# HV.net
KiCad netlist of a schematic drawn in EAGLE
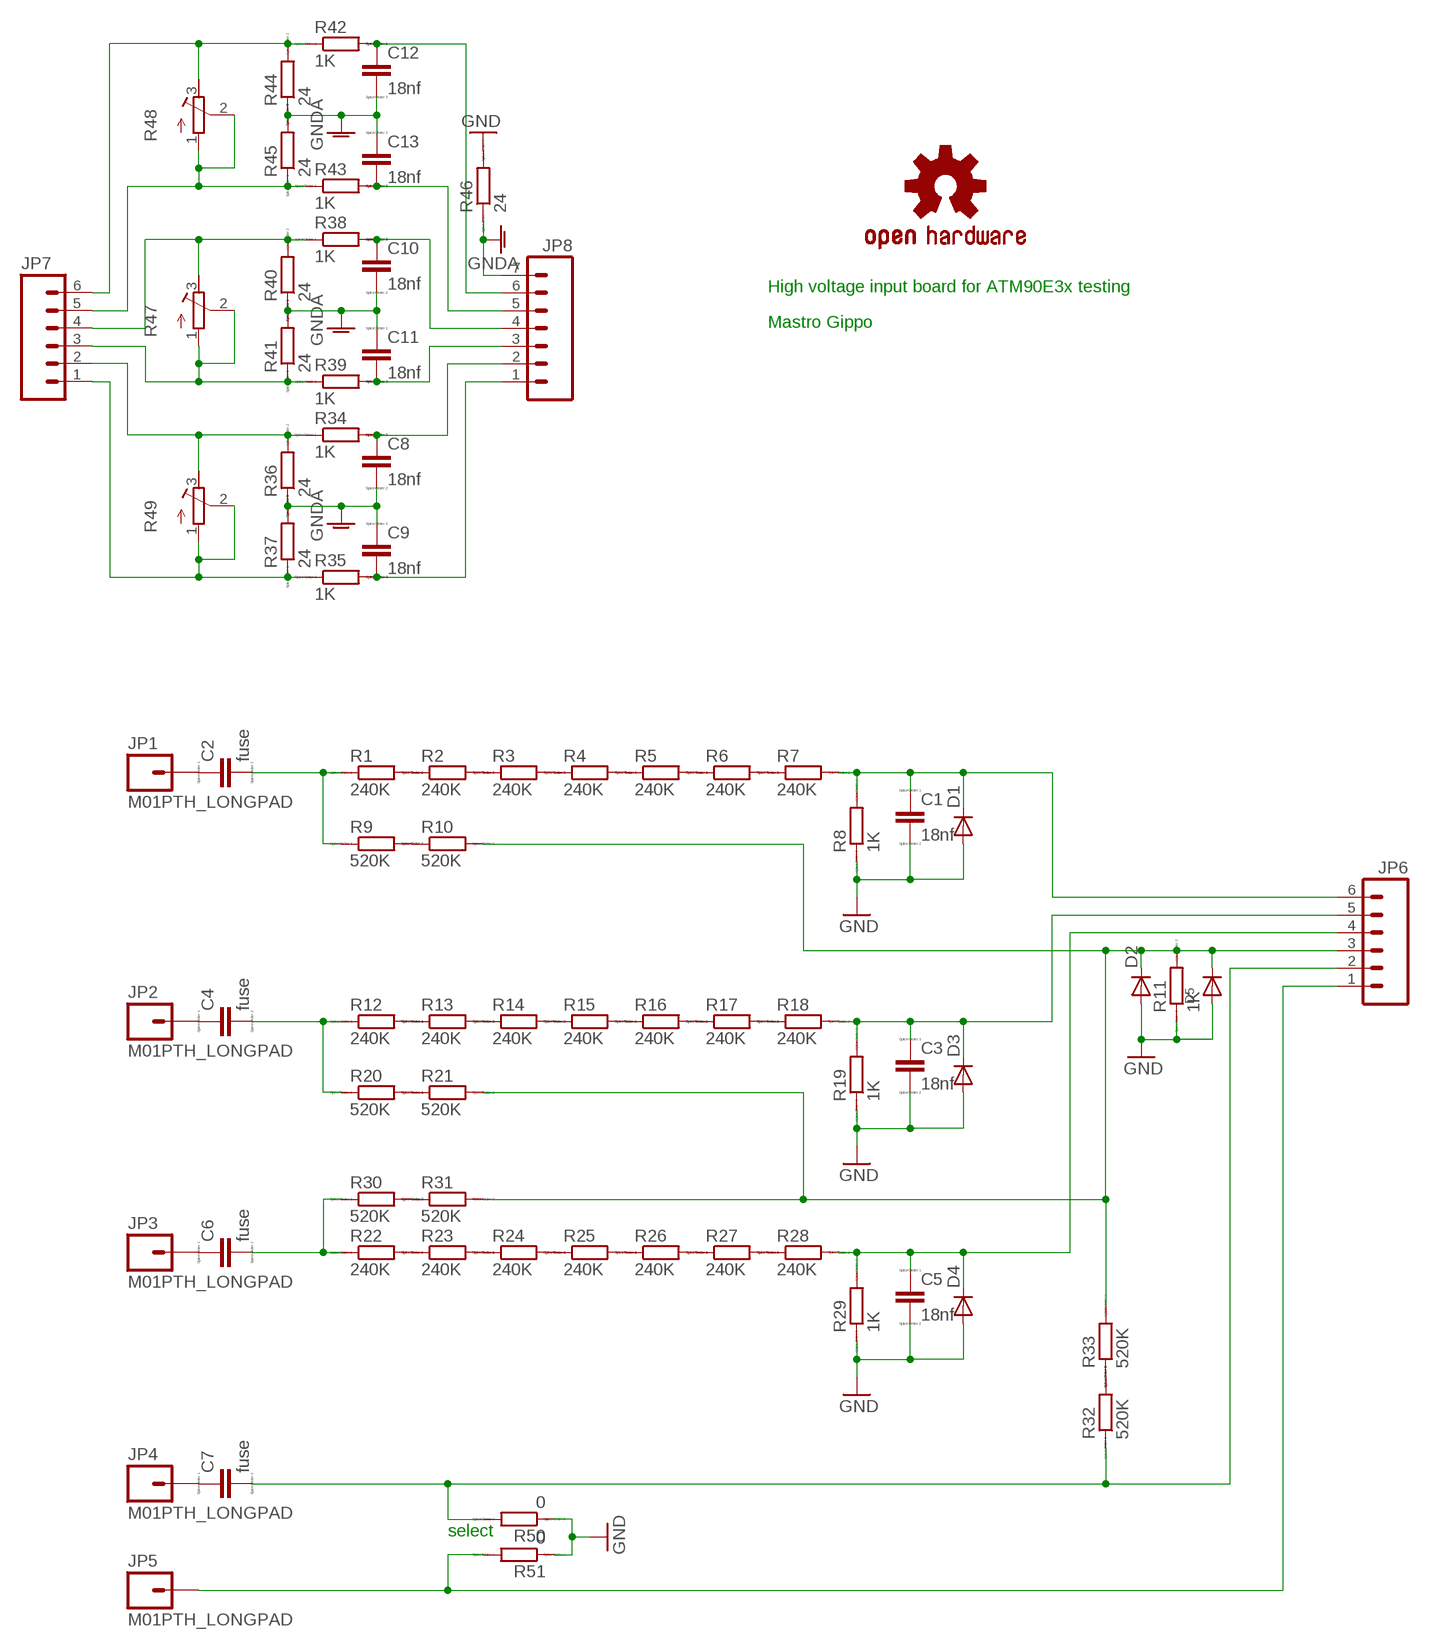
[diagram p0: schematic, sheet 1]

(export (version "E")
  (design (tool "Eeschema 10.0.6"))
  (components
    (comp (ref "C1")
      (value "18nf")
      (footprint "eagle-import:C0805K")
      (libsource (lib "eagle-import") (part "C-EUC0805K"))
    )
    (comp (ref "C2")
      (value "fuse")
      (footprint "eagle-import:C050-025X075")
      (libsource (lib "eagle-import") (part "C-EU050-025X075"))
    )
    (comp (ref "C3")
      (value "18nf")
      (footprint "eagle-import:C0805K")
      (libsource (lib "eagle-import") (part "C-EUC0805K"))
    )
    (comp (ref "C4")
      (value "fuse")
      (footprint "eagle-import:C050-025X075")
      (libsource (lib "eagle-import") (part "C-EU050-025X075"))
    )
    (comp (ref "C5")
      (value "18nf")
      (footprint "eagle-import:C0805K")
      (libsource (lib "eagle-import") (part "C-EUC0805K"))
    )
    (comp (ref "C6")
      (value "fuse")
      (footprint "eagle-import:C050-025X075")
      (libsource (lib "eagle-import") (part "C-EU050-025X075"))
    )
    (comp (ref "C7")
      (value "fuse")
      (footprint "eagle-import:C050-025X075")
      (libsource (lib "eagle-import") (part "C-EU050-025X075"))
    )
    (comp (ref "C8")
      (value "18nf")
      (footprint "eagle-import:C0805K")
      (libsource (lib "eagle-import") (part "C-EUC0805K"))
    )
    (comp (ref "C9")
      (value "18nf")
      (footprint "eagle-import:C0805K")
      (libsource (lib "eagle-import") (part "C-EUC0805K"))
    )
    (comp (ref "C10")
      (value "18nf")
      (footprint "eagle-import:C0805K")
      (libsource (lib "eagle-import") (part "C-EUC0805K"))
    )
    (comp (ref "C11")
      (value "18nf")
      (footprint "eagle-import:C0805K")
      (libsource (lib "eagle-import") (part "C-EUC0805K"))
    )
    (comp (ref "C12")
      (value "18nf")
      (footprint "eagle-import:C0805K")
      (libsource (lib "eagle-import") (part "C-EUC0805K"))
    )
    (comp (ref "C13")
      (value "18nf")
      (footprint "eagle-import:C0805K")
      (libsource (lib "eagle-import") (part "C-EUC0805K"))
    )
    (comp (ref "D1")
      (value "DIODEHV")
      (footprint "eagle-import:DIODE-HV")
      (libsource (lib "eagle-import") (part "DIODEHV"))
    )
    (comp (ref "D2")
      (value "DIODEHV")
      (footprint "eagle-import:DIODE-HV")
      (libsource (lib "eagle-import") (part "DIODEHV"))
    )
    (comp (ref "D3")
      (value "DIODEHV")
      (footprint "eagle-import:DIODE-HV")
      (libsource (lib "eagle-import") (part "DIODEHV"))
    )
    (comp (ref "D4")
      (value "DIODEHV")
      (footprint "eagle-import:DIODE-HV")
      (libsource (lib "eagle-import") (part "DIODEHV"))
    )
    (comp (ref "D5")
      (value "DIODE_SOD-123FL")
      (footprint "eagle-import:SOD-123FL")
      (libsource (lib "eagle-import") (part "DIODE_SOD-123FL"))
    )
    (comp (ref "JP1")
      (value "M01PTH_LONGPAD")
      (footprint "eagle-import:1X01_LONGPAD")
      (libsource (lib "eagle-import") (part "M01PTH_LONGPAD"))
    )
    (comp (ref "JP2")
      (value "M01PTH_LONGPAD")
      (footprint "eagle-import:1X01_LONGPAD")
      (libsource (lib "eagle-import") (part "M01PTH_LONGPAD"))
    )
    (comp (ref "JP3")
      (value "M01PTH_LONGPAD")
      (footprint "eagle-import:1X01_LONGPAD")
      (libsource (lib "eagle-import") (part "M01PTH_LONGPAD"))
    )
    (comp (ref "JP4")
      (value "M01PTH_LONGPAD")
      (footprint "eagle-import:1X01_LONGPAD")
      (libsource (lib "eagle-import") (part "M01PTH_LONGPAD"))
    )
    (comp (ref "JP5")
      (value "M01PTH_LONGPAD")
      (footprint "eagle-import:1X01_LONGPAD")
      (libsource (lib "eagle-import") (part "M01PTH_LONGPAD"))
    )
    (comp (ref "JP6")
      (value "M06LONGPADS")
      (footprint "eagle-import:1X06_LONGPADS")
      (libsource (lib "eagle-import") (part "M06LONGPADS"))
    )
    (comp (ref "JP7")
      (value "M06LONGPADS")
      (footprint "eagle-import:1X06_LONGPADS")
      (libsource (lib "eagle-import") (part "M06LONGPADS"))
    )
    (comp (ref "JP8")
      (value "M07LONGPADS")
      (footprint "eagle-import:1X07_LONGPADS")
      (libsource (lib "eagle-import") (part "M07LONGPADS"))
    )
    (comp (ref "R1")
      (value "240K")
      (footprint "eagle-import:R0805")
      (libsource (lib "eagle-import") (part "R-EU_R0805"))
    )
    (comp (ref "R2")
      (value "240K")
      (footprint "eagle-import:R0805")
      (libsource (lib "eagle-import") (part "R-EU_R0805"))
    )
    (comp (ref "R3")
      (value "240K")
      (footprint "eagle-import:R0805")
      (libsource (lib "eagle-import") (part "R-EU_R0805"))
    )
    (comp (ref "R4")
      (value "240K")
      (footprint "eagle-import:R0805")
      (libsource (lib "eagle-import") (part "R-EU_R0805"))
    )
    (comp (ref "R5")
      (value "240K")
      (footprint "eagle-import:R0805")
      (libsource (lib "eagle-import") (part "R-EU_R0805"))
    )
    (comp (ref "R6")
      (value "240K")
      (footprint "eagle-import:R0805")
      (libsource (lib "eagle-import") (part "R-EU_R0805"))
    )
    (comp (ref "R7")
      (value "240K")
      (footprint "eagle-import:R0805")
      (libsource (lib "eagle-import") (part "R-EU_R0805"))
    )
    (comp (ref "R8")
      (value "1K")
      (footprint "eagle-import:R0805")
      (libsource (lib "eagle-import") (part "R-EU_R0805"))
    )
    (comp (ref "R9")
      (value "520K")
      (footprint "eagle-import:R0805")
      (libsource (lib "eagle-import") (part "R-EU_R0805"))
    )
    (comp (ref "R10")
      (value "520K")
      (footprint "eagle-import:R0805")
      (libsource (lib "eagle-import") (part "R-EU_R0805"))
    )
    (comp (ref "R11")
      (value "1K")
      (footprint "eagle-import:R0805")
      (libsource (lib "eagle-import") (part "R-EU_R0805"))
    )
    (comp (ref "R12")
      (value "240K")
      (footprint "eagle-import:R0805")
      (libsource (lib "eagle-import") (part "R-EU_R0805"))
    )
    (comp (ref "R13")
      (value "240K")
      (footprint "eagle-import:R0805")
      (libsource (lib "eagle-import") (part "R-EU_R0805"))
    )
    (comp (ref "R14")
      (value "240K")
      (footprint "eagle-import:R0805")
      (libsource (lib "eagle-import") (part "R-EU_R0805"))
    )
    (comp (ref "R15")
      (value "240K")
      (footprint "eagle-import:R0805")
      (libsource (lib "eagle-import") (part "R-EU_R0805"))
    )
    (comp (ref "R16")
      (value "240K")
      (footprint "eagle-import:R0805")
      (libsource (lib "eagle-import") (part "R-EU_R0805"))
    )
    (comp (ref "R17")
      (value "240K")
      (footprint "eagle-import:R0805")
      (libsource (lib "eagle-import") (part "R-EU_R0805"))
    )
    (comp (ref "R18")
      (value "240K")
      (footprint "eagle-import:R0805")
      (libsource (lib "eagle-import") (part "R-EU_R0805"))
    )
    (comp (ref "R19")
      (value "1K")
      (footprint "eagle-import:R0805")
      (libsource (lib "eagle-import") (part "R-EU_R0805"))
    )
    (comp (ref "R20")
      (value "520K")
      (footprint "eagle-import:R0805")
      (libsource (lib "eagle-import") (part "R-EU_R0805"))
    )
    (comp (ref "R21")
      (value "520K")
      (footprint "eagle-import:R0805")
      (libsource (lib "eagle-import") (part "R-EU_R0805"))
    )
    (comp (ref "R22")
      (value "240K")
      (footprint "eagle-import:R0805")
      (libsource (lib "eagle-import") (part "R-EU_R0805"))
    )
    (comp (ref "R23")
      (value "240K")
      (footprint "eagle-import:R0805")
      (libsource (lib "eagle-import") (part "R-EU_R0805"))
    )
    (comp (ref "R24")
      (value "240K")
      (footprint "eagle-import:R0805")
      (libsource (lib "eagle-import") (part "R-EU_R0805"))
    )
    (comp (ref "R25")
      (value "240K")
      (footprint "eagle-import:R0805")
      (libsource (lib "eagle-import") (part "R-EU_R0805"))
    )
    (comp (ref "R26")
      (value "240K")
      (footprint "eagle-import:R0805")
      (libsource (lib "eagle-import") (part "R-EU_R0805"))
    )
    (comp (ref "R27")
      (value "240K")
      (footprint "eagle-import:R0805")
      (libsource (lib "eagle-import") (part "R-EU_R0805"))
    )
    (comp (ref "R28")
      (value "240K")
      (footprint "eagle-import:R0805")
      (libsource (lib "eagle-import") (part "R-EU_R0805"))
    )
    (comp (ref "R29")
      (value "1K")
      (footprint "eagle-import:R0805")
      (libsource (lib "eagle-import") (part "R-EU_R0805"))
    )
    (comp (ref "R30")
      (value "520K")
      (footprint "eagle-import:R0805")
      (libsource (lib "eagle-import") (part "R-EU_R0805"))
    )
    (comp (ref "R31")
      (value "520K")
      (footprint "eagle-import:R0805")
      (libsource (lib "eagle-import") (part "R-EU_R0805"))
    )
    (comp (ref "R32")
      (value "520K")
      (footprint "eagle-import:R0805")
      (libsource (lib "eagle-import") (part "R-EU_R0805"))
    )
    (comp (ref "R33")
      (value "520K")
      (footprint "eagle-import:R0805")
      (libsource (lib "eagle-import") (part "R-EU_R0805"))
    )
    (comp (ref "R34")
      (value "1K")
      (footprint "eagle-import:R0805")
      (libsource (lib "eagle-import") (part "R-EU_R0805"))
    )
    (comp (ref "R35")
      (value "1K")
      (footprint "eagle-import:R0805")
      (libsource (lib "eagle-import") (part "R-EU_R0805"))
    )
    (comp (ref "R36")
      (value "24")
      (footprint "eagle-import:R0805")
      (libsource (lib "eagle-import") (part "R-EU_R0805"))
    )
    (comp (ref "R37")
      (value "24")
      (footprint "eagle-import:R0805")
      (libsource (lib "eagle-import") (part "R-EU_R0805"))
    )
    (comp (ref "R38")
      (value "1K")
      (footprint "eagle-import:R0805")
      (libsource (lib "eagle-import") (part "R-EU_R0805"))
    )
    (comp (ref "R39")
      (value "1K")
      (footprint "eagle-import:R0805")
      (libsource (lib "eagle-import") (part "R-EU_R0805"))
    )
    (comp (ref "R40")
      (value "24")
      (footprint "eagle-import:R0805")
      (libsource (lib "eagle-import") (part "R-EU_R0805"))
    )
    (comp (ref "R41")
      (value "24")
      (footprint "eagle-import:R0805")
      (libsource (lib "eagle-import") (part "R-EU_R0805"))
    )
    (comp (ref "R42")
      (value "1K")
      (footprint "eagle-import:R0805")
      (libsource (lib "eagle-import") (part "R-EU_R0805"))
    )
    (comp (ref "R43")
      (value "1K")
      (footprint "eagle-import:R0805")
      (libsource (lib "eagle-import") (part "R-EU_R0805"))
    )
    (comp (ref "R44")
      (value "24")
      (footprint "eagle-import:R0805")
      (libsource (lib "eagle-import") (part "R-EU_R0805"))
    )
    (comp (ref "R45")
      (value "24")
      (footprint "eagle-import:R0805")
      (libsource (lib "eagle-import") (part "R-EU_R0805"))
    )
    (comp (ref "R46")
      (value "24")
      (footprint "eagle-import:R0805")
      (libsource (lib "eagle-import") (part "R-EU_R0805"))
    )
    (comp (ref "R47")
      (value "R-TRIMM3224J")
      (footprint "eagle-import:RTRIM3224J")
      (libsource (lib "eagle-import") (part "R-TRIMM3224J"))
    )
    (comp (ref "R48")
      (value "R-TRIMM3224J")
      (footprint "eagle-import:RTRIM3224J")
      (libsource (lib "eagle-import") (part "R-TRIMM3224J"))
    )
    (comp (ref "R49")
      (value "R-TRIMM3224J")
      (footprint "eagle-import:RTRIM3224J")
      (libsource (lib "eagle-import") (part "R-TRIMM3224J"))
    )
    (comp (ref "R50")
      (value "0")
      (footprint "eagle-import:R0805")
      (libsource (lib "eagle-import") (part "R-EU_R0805"))
    )
    (comp (ref "R51")
      (value "0")
      (footprint "eagle-import:R0805")
      (libsource (lib "eagle-import") (part "R-EU_R0805"))
    )
    (comp (ref "U$1")
      (value "OSHW-LOGOS")
      (footprint "eagle-import:OSHW-LOGO-S")
      (libsource (lib "eagle-import") (part "OSHW-LOGOS"))
    )
  )
  (nets
    (net (code "1") (name "GND") (class "Default")
      (node (ref "C1") (pin "2") (pinfunction "2_2") (pintype "passive"))
      (node (ref "C3") (pin "2") (pinfunction "2_2") (pintype "passive"))
      (node (ref "C5") (pin "2") (pinfunction "2_2") (pintype "passive"))
      (node (ref "D1") (pin "A") (pinfunction "A_A") (pintype "passive"))
      (node (ref "D2") (pin "A") (pinfunction "A_A") (pintype "passive"))
      (node (ref "D3") (pin "A") (pinfunction "A_A") (pintype "passive"))
      (node (ref "D4") (pin "A") (pinfunction "A_A") (pintype "passive"))
      (node (ref "D5") (pin "A") (pinfunction "A_A") (pintype "passive"))
      (node (ref "R11") (pin "1") (pinfunction "1_1") (pintype "passive"))
      (node (ref "R19") (pin "1") (pinfunction "1_1") (pintype "passive"))
      (node (ref "R29") (pin "1") (pinfunction "1_1") (pintype "passive"))
      (node (ref "R46") (pin "2") (pinfunction "2_2") (pintype "passive"))
      (node (ref "R50") (pin "1") (pinfunction "1_1") (pintype "passive"))
      (node (ref "R51") (pin "1") (pinfunction "1_1") (pintype "passive"))
      (node (ref "R8") (pin "1") (pinfunction "1_1") (pintype "passive"))
    )
    (net (code "2") (name "GNDA") (class "Default")
      (node (ref "C10") (pin "2") (pinfunction "2_2") (pintype "passive"))
      (node (ref "C11") (pin "1") (pinfunction "1_1") (pintype "passive"))
      (node (ref "C12") (pin "2") (pinfunction "2_2") (pintype "passive"))
      (node (ref "C13") (pin "1") (pinfunction "1_1") (pintype "passive"))
      (node (ref "C8") (pin "2") (pinfunction "2_2") (pintype "passive"))
      (node (ref "C9") (pin "1") (pinfunction "1_1") (pintype "passive"))
      (node (ref "JP8") (pin "7") (pinfunction "7_7") (pintype "passive"))
      (node (ref "R36") (pin "1") (pinfunction "1_1") (pintype "passive"))
      (node (ref "R37") (pin "2") (pinfunction "2_2") (pintype "passive"))
      (node (ref "R40") (pin "1") (pinfunction "1_1") (pintype "passive"))
      (node (ref "R41") (pin "2") (pinfunction "2_2") (pintype "passive"))
      (node (ref "R44") (pin "1") (pinfunction "1_1") (pintype "passive"))
      (node (ref "R45") (pin "2") (pinfunction "2_2") (pintype "passive"))
      (node (ref "R46") (pin "1") (pinfunction "1_1") (pintype "passive"))
    )
    (net (code "3") (name "Net-(C1-Pad1)") (class "Default")
      (node (ref "C1") (pin "1") (pinfunction "1_1") (pintype "passive"))
      (node (ref "D1") (pin "C") (pinfunction "C_C") (pintype "passive"))
      (node (ref "JP6") (pin "6") (pinfunction "6_6") (pintype "passive"))
      (node (ref "R7") (pin "2") (pinfunction "2_2") (pintype "passive"))
      (node (ref "R8") (pin "2") (pinfunction "2_2") (pintype "passive"))
    )
    (net (code "4") (name "Net-(C2-Pad1)") (class "Default")
      (node (ref "C2") (pin "1") (pinfunction "1_1") (pintype "passive"))
      (node (ref "JP1") (pin "1") (pinfunction "1_1") (pintype "passive"))
    )
    (net (code "5") (name "Net-(C2-Pad2)") (class "Default")
      (node (ref "C2") (pin "2") (pinfunction "2_2") (pintype "passive"))
      (node (ref "R1") (pin "1") (pinfunction "1_1") (pintype "passive"))
      (node (ref "R9") (pin "1") (pinfunction "1_1") (pintype "passive"))
    )
    (net (code "6") (name "Net-(C3-Pad1)") (class "Default")
      (node (ref "C3") (pin "1") (pinfunction "1_1") (pintype "passive"))
      (node (ref "D3") (pin "C") (pinfunction "C_C") (pintype "passive"))
      (node (ref "JP6") (pin "5") (pinfunction "5_5") (pintype "passive"))
      (node (ref "R18") (pin "2") (pinfunction "2_2") (pintype "passive"))
      (node (ref "R19") (pin "2") (pinfunction "2_2") (pintype "passive"))
    )
    (net (code "7") (name "Net-(C4-Pad1)") (class "Default")
      (node (ref "C4") (pin "1") (pinfunction "1_1") (pintype "passive"))
      (node (ref "JP2") (pin "1") (pinfunction "1_1") (pintype "passive"))
    )
    (net (code "8") (name "Net-(C4-Pad2)") (class "Default")
      (node (ref "C4") (pin "2") (pinfunction "2_2") (pintype "passive"))
      (node (ref "R12") (pin "1") (pinfunction "1_1") (pintype "passive"))
      (node (ref "R20") (pin "1") (pinfunction "1_1") (pintype "passive"))
    )
    (net (code "9") (name "Net-(C5-Pad1)") (class "Default")
      (node (ref "C5") (pin "1") (pinfunction "1_1") (pintype "passive"))
      (node (ref "D4") (pin "C") (pinfunction "C_C") (pintype "passive"))
      (node (ref "JP6") (pin "4") (pinfunction "4_4") (pintype "passive"))
      (node (ref "R28") (pin "2") (pinfunction "2_2") (pintype "passive"))
      (node (ref "R29") (pin "2") (pinfunction "2_2") (pintype "passive"))
    )
    (net (code "10") (name "Net-(C6-Pad1)") (class "Default")
      (node (ref "C6") (pin "1") (pinfunction "1_1") (pintype "passive"))
      (node (ref "JP3") (pin "1") (pinfunction "1_1") (pintype "passive"))
    )
    (net (code "11") (name "Net-(C6-Pad2)") (class "Default")
      (node (ref "C6") (pin "2") (pinfunction "2_2") (pintype "passive"))
      (node (ref "R22") (pin "1") (pinfunction "1_1") (pintype "passive"))
      (node (ref "R30") (pin "1") (pinfunction "1_1") (pintype "passive"))
    )
    (net (code "12") (name "Net-(C7-Pad1)") (class "Default")
      (node (ref "C7") (pin "1") (pinfunction "1_1") (pintype "passive"))
      (node (ref "JP4") (pin "1") (pinfunction "1_1") (pintype "passive"))
    )
    (net (code "13") (name "Net-(C7-Pad2)") (class "Default")
      (node (ref "C7") (pin "2") (pinfunction "2_2") (pintype "passive"))
      (node (ref "JP6") (pin "2") (pinfunction "2_2") (pintype "passive"))
      (node (ref "R32") (pin "1") (pinfunction "1_1") (pintype "passive"))
      (node (ref "R50") (pin "2") (pinfunction "2_2") (pintype "passive"))
    )
    (net (code "14") (name "Net-(C8-Pad1)") (class "Default")
      (node (ref "C8") (pin "1") (pinfunction "1_1") (pintype "passive"))
      (node (ref "JP8") (pin "2") (pinfunction "2_2") (pintype "passive"))
      (node (ref "R34") (pin "2") (pinfunction "2_2") (pintype "passive"))
    )
    (net (code "15") (name "Net-(C9-Pad2)") (class "Default")
      (node (ref "C9") (pin "2") (pinfunction "2_2") (pintype "passive"))
      (node (ref "JP8") (pin "1") (pinfunction "1_1") (pintype "passive"))
      (node (ref "R35") (pin "2") (pinfunction "2_2") (pintype "passive"))
    )
    (net (code "16") (name "Net-(C10-Pad1)") (class "Default")
      (node (ref "C10") (pin "1") (pinfunction "1_1") (pintype "passive"))
      (node (ref "JP8") (pin "4") (pinfunction "4_4") (pintype "passive"))
      (node (ref "R38") (pin "2") (pinfunction "2_2") (pintype "passive"))
    )
    (net (code "17") (name "Net-(C11-Pad2)") (class "Default")
      (node (ref "C11") (pin "2") (pinfunction "2_2") (pintype "passive"))
      (node (ref "JP8") (pin "3") (pinfunction "3_3") (pintype "passive"))
      (node (ref "R39") (pin "2") (pinfunction "2_2") (pintype "passive"))
    )
    (net (code "18") (name "Net-(C12-Pad1)") (class "Default")
      (node (ref "C12") (pin "1") (pinfunction "1_1") (pintype "passive"))
      (node (ref "JP8") (pin "6") (pinfunction "6_6") (pintype "passive"))
      (node (ref "R42") (pin "2") (pinfunction "2_2") (pintype "passive"))
    )
    (net (code "19") (name "Net-(C13-Pad2)") (class "Default")
      (node (ref "C13") (pin "2") (pinfunction "2_2") (pintype "passive"))
      (node (ref "JP8") (pin "5") (pinfunction "5_5") (pintype "passive"))
      (node (ref "R43") (pin "2") (pinfunction "2_2") (pintype "passive"))
    )
    (net (code "20") (name "Net-(D2-PadC)") (class "Default")
      (node (ref "D2") (pin "C") (pinfunction "C_C") (pintype "passive"))
      (node (ref "D5") (pin "C") (pinfunction "C_C") (pintype "passive"))
      (node (ref "JP6") (pin "3") (pinfunction "3_3") (pintype "passive"))
      (node (ref "R10") (pin "2") (pinfunction "2_2") (pintype "passive"))
      (node (ref "R11") (pin "2") (pinfunction "2_2") (pintype "passive"))
      (node (ref "R21") (pin "2") (pinfunction "2_2") (pintype "passive"))
      (node (ref "R31") (pin "2") (pinfunction "2_2") (pintype "passive"))
      (node (ref "R33") (pin "2") (pinfunction "2_2") (pintype "passive"))
    )
    (net (code "21") (name "Net-(JP5-Pad1)") (class "Default")
      (node (ref "JP5") (pin "1") (pinfunction "1_1") (pintype "passive"))
      (node (ref "JP6") (pin "1") (pinfunction "1_1") (pintype "passive"))
      (node (ref "R51") (pin "2") (pinfunction "2_2") (pintype "passive"))
    )
    (net (code "22") (name "Net-(R1-Pad2)") (class "Default")
      (node (ref "R1") (pin "2") (pinfunction "2_2") (pintype "passive"))
      (node (ref "R2") (pin "1") (pinfunction "1_1") (pintype "passive"))
    )
    (net (code "23") (name "Net-(R2-Pad2)") (class "Default")
      (node (ref "R2") (pin "2") (pinfunction "2_2") (pintype "passive"))
      (node (ref "R3") (pin "1") (pinfunction "1_1") (pintype "passive"))
    )
    (net (code "24") (name "Net-(R3-Pad2)") (class "Default")
      (node (ref "R3") (pin "2") (pinfunction "2_2") (pintype "passive"))
      (node (ref "R4") (pin "1") (pinfunction "1_1") (pintype "passive"))
    )
    (net (code "25") (name "Net-(R4-Pad2)") (class "Default")
      (node (ref "R4") (pin "2") (pinfunction "2_2") (pintype "passive"))
      (node (ref "R5") (pin "1") (pinfunction "1_1") (pintype "passive"))
    )
    (net (code "26") (name "Net-(R5-Pad2)") (class "Default")
      (node (ref "R5") (pin "2") (pinfunction "2_2") (pintype "passive"))
      (node (ref "R6") (pin "1") (pinfunction "1_1") (pintype "passive"))
    )
    (net (code "27") (name "Net-(R6-Pad2)") (class "Default")
      (node (ref "R6") (pin "2") (pinfunction "2_2") (pintype "passive"))
      (node (ref "R7") (pin "1") (pinfunction "1_1") (pintype "passive"))
    )
    (net (code "28") (name "Net-(R10-Pad1)") (class "Default")
      (node (ref "R10") (pin "1") (pinfunction "1_1") (pintype "passive"))
      (node (ref "R9") (pin "2") (pinfunction "2_2") (pintype "passive"))
    )
    (net (code "29") (name "Net-(R12-Pad2)") (class "Default")
      (node (ref "R12") (pin "2") (pinfunction "2_2") (pintype "passive"))
      (node (ref "R13") (pin "1") (pinfunction "1_1") (pintype "passive"))
    )
    (net (code "30") (name "Net-(R13-Pad2)") (class "Default")
      (node (ref "R13") (pin "2") (pinfunction "2_2") (pintype "passive"))
      (node (ref "R14") (pin "1") (pinfunction "1_1") (pintype "passive"))
    )
    (net (code "31") (name "Net-(R14-Pad2)") (class "Default")
      (node (ref "R14") (pin "2") (pinfunction "2_2") (pintype "passive"))
      (node (ref "R15") (pin "1") (pinfunction "1_1") (pintype "passive"))
    )
    (net (code "32") (name "Net-(R15-Pad2)") (class "Default")
      (node (ref "R15") (pin "2") (pinfunction "2_2") (pintype "passive"))
      (node (ref "R16") (pin "1") (pinfunction "1_1") (pintype "passive"))
    )
    (net (code "33") (name "Net-(R16-Pad2)") (class "Default")
      (node (ref "R16") (pin "2") (pinfunction "2_2") (pintype "passive"))
      (node (ref "R17") (pin "1") (pinfunction "1_1") (pintype "passive"))
    )
    (net (code "34") (name "Net-(R17-Pad2)") (class "Default")
      (node (ref "R17") (pin "2") (pinfunction "2_2") (pintype "passive"))
      (node (ref "R18") (pin "1") (pinfunction "1_1") (pintype "passive"))
    )
    (net (code "35") (name "Net-(R20-Pad2)") (class "Default")
      (node (ref "R20") (pin "2") (pinfunction "2_2") (pintype "passive"))
      (node (ref "R21") (pin "1") (pinfunction "1_1") (pintype "passive"))
    )
    (net (code "36") (name "Net-(R22-Pad2)") (class "Default")
      (node (ref "R22") (pin "2") (pinfunction "2_2") (pintype "passive"))
      (node (ref "R23") (pin "1") (pinfunction "1_1") (pintype "passive"))
    )
    (net (code "37") (name "Net-(R23-Pad2)") (class "Default")
      (node (ref "R23") (pin "2") (pinfunction "2_2") (pintype "passive"))
      (node (ref "R24") (pin "1") (pinfunction "1_1") (pintype "passive"))
    )
    (net (code "38") (name "Net-(R24-Pad2)") (class "Default")
      (node (ref "R24") (pin "2") (pinfunction "2_2") (pintype "passive"))
      (node (ref "R25") (pin "1") (pinfunction "1_1") (pintype "passive"))
    )
    (net (code "39") (name "Net-(R25-Pad2)") (class "Default")
      (node (ref "R25") (pin "2") (pinfunction "2_2") (pintype "passive"))
      (node (ref "R26") (pin "1") (pinfunction "1_1") (pintype "passive"))
    )
    (net (code "40") (name "Net-(R26-Pad2)") (class "Default")
      (node (ref "R26") (pin "2") (pinfunction "2_2") (pintype "passive"))
      (node (ref "R27") (pin "1") (pinfunction "1_1") (pintype "passive"))
    )
    (net (code "41") (name "Net-(R27-Pad2)") (class "Default")
      (node (ref "R27") (pin "2") (pinfunction "2_2") (pintype "passive"))
      (node (ref "R28") (pin "1") (pinfunction "1_1") (pintype "passive"))
    )
    (net (code "42") (name "Net-(R30-Pad2)") (class "Default")
      (node (ref "R30") (pin "2") (pinfunction "2_2") (pintype "passive"))
      (node (ref "R31") (pin "1") (pinfunction "1_1") (pintype "passive"))
    )
    (net (code "43") (name "Net-(R32-Pad2)") (class "Default")
      (node (ref "R32") (pin "2") (pinfunction "2_2") (pintype "passive"))
      (node (ref "R33") (pin "1") (pinfunction "1_1") (pintype "passive"))
    )
    (net (code "44") (name "Net-(R47-A)") (class "Default")
      (node (ref "JP7") (pin "4") (pinfunction "4_4") (pintype "passive"))
      (node (ref "R38") (pin "1") (pinfunction "1_1") (pintype "passive"))
      (node (ref "R40") (pin "2") (pinfunction "2_2") (pintype "passive"))
      (node (ref "R47") (pin "3") (pinfunction "A_3") (pintype "passive"))
    )
    (net (code "45") (name "Net-(R47-E)") (class "Default")
      (node (ref "JP7") (pin "3") (pinfunction "3_3") (pintype "passive"))
      (node (ref "R39") (pin "1") (pinfunction "1_1") (pintype "passive"))
      (node (ref "R41") (pin "1") (pinfunction "1_1") (pintype "passive"))
      (node (ref "R47") (pin "1") (pinfunction "E_1") (pintype "passive"))
      (node (ref "R47") (pin "2") (pinfunction "S_2") (pintype "passive"))
    )
    (net (code "46") (name "Net-(R48-A)") (class "Default")
      (node (ref "JP7") (pin "6") (pinfunction "6_6") (pintype "passive"))
      (node (ref "R42") (pin "1") (pinfunction "1_1") (pintype "passive"))
      (node (ref "R44") (pin "2") (pinfunction "2_2") (pintype "passive"))
      (node (ref "R48") (pin "3") (pinfunction "A_3") (pintype "passive"))
    )
    (net (code "47") (name "Net-(R48-E)") (class "Default")
      (node (ref "JP7") (pin "5") (pinfunction "5_5") (pintype "passive"))
      (node (ref "R43") (pin "1") (pinfunction "1_1") (pintype "passive"))
      (node (ref "R45") (pin "1") (pinfunction "1_1") (pintype "passive"))
      (node (ref "R48") (pin "1") (pinfunction "E_1") (pintype "passive"))
      (node (ref "R48") (pin "2") (pinfunction "S_2") (pintype "passive"))
    )
    (net (code "48") (name "Net-(R49-A)") (class "Default")
      (node (ref "JP7") (pin "2") (pinfunction "2_2") (pintype "passive"))
      (node (ref "R34") (pin "1") (pinfunction "1_1") (pintype "passive"))
      (node (ref "R36") (pin "2") (pinfunction "2_2") (pintype "passive"))
      (node (ref "R49") (pin "3") (pinfunction "A_3") (pintype "passive"))
    )
    (net (code "49") (name "Net-(R49-E)") (class "Default")
      (node (ref "JP7") (pin "1") (pinfunction "1_1") (pintype "passive"))
      (node (ref "R35") (pin "1") (pinfunction "1_1") (pintype "passive"))
      (node (ref "R37") (pin "1") (pinfunction "1_1") (pintype "passive"))
      (node (ref "R49") (pin "1") (pinfunction "E_1") (pintype "passive"))
      (node (ref "R49") (pin "2") (pinfunction "S_2") (pintype "passive"))
    )
  )
)
